# uC_pwr.net
KiCad netlist of a schematic drawn in Altium Designer
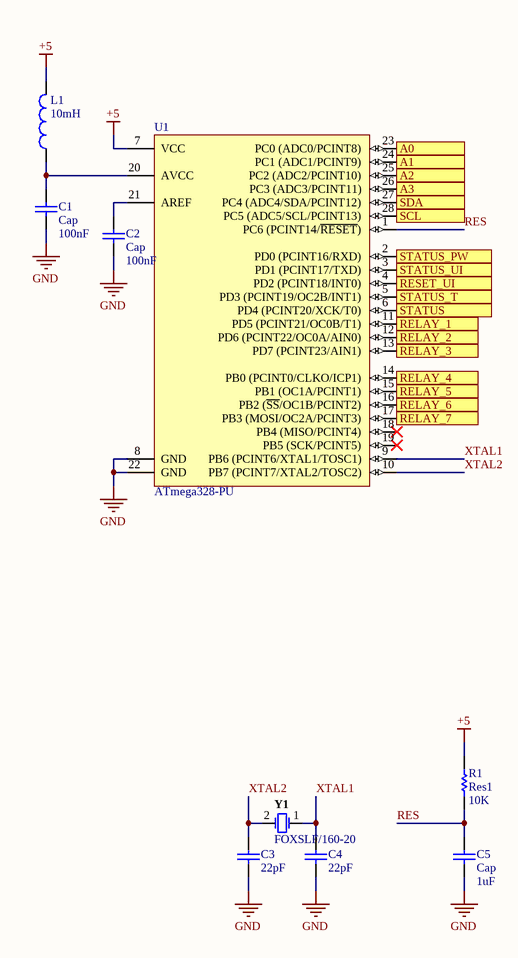
[diagram p0: uC_pwr.SchDoc]

(export (version "E")
  (design (tool "Eeschema 10.0.6"))
  (components
    (comp (ref "C1")
      (value "Cap")
      (footprint "RAD-0.3")
      (description "Capacitor")
      (fields (field (name "ALTIUM_VALUE") "100nF") (field (name "PUBLISHER") "Altium Limited"))
      (libsource (lib "Miscellaneous Devices") (part "Cap"))
    )
    (comp (ref "C2")
      (value "Cap")
      (footprint "RAD-0.3")
      (description "Capacitor")
      (fields (field (name "ALTIUM_VALUE") "100nF") (field (name "PUBLISHER") "Altium Limited"))
      (libsource (lib "Miscellaneous Devices") (part "Cap"))
    )
    (comp (ref "C3")
      (value "22pF")
      (footprint "RAD-0.3")
      (description "Capacitor")
      (fields (field (name "Comment") "Cap") (field (name "PUBLISHER") "Altium Limited"))
      (libsource (lib "Miscellaneous Devices") (part "Cap"))
    )
    (comp (ref "C4")
      (value "22pF")
      (footprint "RAD-0.3")
      (description "Capacitor")
      (fields (field (name "Comment") "Cap") (field (name "PUBLISHER") "Altium Limited"))
      (libsource (lib "Miscellaneous Devices") (part "Cap"))
    )
    (comp (ref "C5")
      (value "Cap")
      (footprint "RAD-0.3")
      (description "Capacitor")
      (fields (field (name "ALTIUM_VALUE") "1uF") (field (name "PUBLISHER") "Altium Limited"))
      (libsource (lib "Miscellaneous Devices") (part "Cap"))
    )
    (comp (ref "L1")
      (value "10mH")
      (footprint "INDR62-500-1100X850X1100")
      (description "Radial Inductor, 10 uH, +/- 10%, 3 A, -55 to 105 degC, 2-Pin THD, RoHS, Bulk")
      (libsource (lib "Altium Content Vault") (part "IND-2"))
    )
    (comp (ref "R1")
      (value "Res1")
      (footprint "AXIAL-0.3")
      (description "Resistor")
      (fields (field (name "ALTIUM_VALUE") "10K") (field (name "PUBLISHER") "Altium Limited"))
      (libsource (lib "Miscellaneous Devices") (part "Res1"))
    )
    (comp (ref "U1")
      (value "ATmega328-PU")
      (footprint "28P3")
      (libsource (lib "Altium Content Vault") (part "MC-8B-ATM48-IL28"))
    )
    (comp (ref "Y1")
      (value "FOXSLF/160-20")
      (footprint "FOX-FOXSLF160-20")
      (description "Resistance Weld Thru-Hole Crystal, 16 MHz, -20 to 70 degC, 2-Pin THD, RoHS, Bulk")
      (fields (field (name "TOLERANCE") "1%"))
      (libsource (lib "Altium Content Vault") (part "XTAL-1-2-2"))
    )
  )
  (nets
    (net (code "1") (name "+5") (class "Default")
      (node (ref "L1") (pin "2") (pinfunction "2_2") (pintype "passive"))
      (node (ref "R1") (pin "2") (pinfunction "2_2") (pintype "passive"))
      (node (ref "U1") (pin "7") (pinfunction "VCC_7") (pintype "power_in"))
    )
    (net (code "2") (name "/A0") (class "Default")
      (node (ref "U1") (pin "23") (pinfunction "PC0_(ADC0/PCINT8)_23") (pintype "bidirectional"))
    )
    (net (code "3") (name "/A1") (class "Default")
      (node (ref "U1") (pin "24") (pinfunction "PC1_(ADC1/PCINT9)_24") (pintype "bidirectional"))
    )
    (net (code "4") (name "/A2") (class "Default")
      (node (ref "U1") (pin "25") (pinfunction "PC2_(ADC2/PCINT10)_25") (pintype "bidirectional"))
    )
    (net (code "5") (name "/A3") (class "Default")
      (node (ref "U1") (pin "26") (pinfunction "PC3_(ADC3/PCINT11)_26") (pintype "bidirectional"))
    )
    (net (code "6") (name "/RELAY_1") (class "Default")
      (node (ref "U1") (pin "11") (pinfunction "PD5_(PCINT21/OC0B/T1)_11") (pintype "bidirectional"))
    )
    (net (code "7") (name "/RELAY_2") (class "Default")
      (node (ref "U1") (pin "12") (pinfunction "PD6_(PCINT22/OC0A/AIN0)_12") (pintype "bidirectional"))
    )
    (net (code "8") (name "/RELAY_3") (class "Default")
      (node (ref "U1") (pin "13") (pinfunction "PD7_(PCINT23/AIN1)_13") (pintype "bidirectional"))
    )
    (net (code "9") (name "/RELAY_4") (class "Default")
      (node (ref "U1") (pin "14") (pinfunction "PB0_(PCINT0/CLKO/ICP1)_14") (pintype "bidirectional"))
    )
    (net (code "10") (name "/RELAY_5") (class "Default")
      (node (ref "U1") (pin "15") (pinfunction "PB1_(OC1A/PCINT1)_15") (pintype "bidirectional"))
    )
    (net (code "11") (name "/RELAY_6") (class "Default")
      (node (ref "U1") (pin "16") (pinfunction "PB2_(~{SS}/OC1B/PCINT2)_16") (pintype "bidirectional"))
    )
    (net (code "12") (name "/RELAY_7") (class "Default")
      (node (ref "U1") (pin "17") (pinfunction "PB3_(MOSI/OC2A/PCINT3)_17") (pintype "bidirectional"))
    )
    (net (code "13") (name "/RES") (class "Default")
      (node (ref "C5") (pin "2") (pinfunction "2_2") (pintype "passive"))
      (node (ref "R1") (pin "1") (pinfunction "1_1") (pintype "passive"))
      (node (ref "U1") (pin "1") (pinfunction "PC6_(PCINT14/~{RESET})_1") (pintype "bidirectional"))
    )
    (net (code "14") (name "/RESET_UI") (class "Default")
      (node (ref "U1") (pin "4") (pinfunction "PD2_(PCINT18/INT0)_4") (pintype "bidirectional"))
    )
    (net (code "15") (name "/SCL") (class "Default")
      (node (ref "U1") (pin "28") (pinfunction "PC5_(ADC5/SCL/PCINT13)_28") (pintype "bidirectional"))
    )
    (net (code "16") (name "/SDA") (class "Default")
      (node (ref "U1") (pin "27") (pinfunction "PC4_(ADC4/SDA/PCINT12)_27") (pintype "bidirectional"))
    )
    (net (code "17") (name "/STATUS") (class "Default")
      (node (ref "U1") (pin "6") (pinfunction "PD4_(PCINT20/XCK/T0)_6") (pintype "bidirectional"))
    )
    (net (code "18") (name "/STATUS_PW") (class "Default")
      (node (ref "U1") (pin "2") (pinfunction "PD0_(PCINT16/RXD)_2") (pintype "bidirectional"))
    )
    (net (code "19") (name "/STATUS_T") (class "Default")
      (node (ref "U1") (pin "5") (pinfunction "PD3_(PCINT19/OC2B/INT1)_5") (pintype "bidirectional"))
    )
    (net (code "20") (name "/STATUS_UI") (class "Default")
      (node (ref "U1") (pin "3") (pinfunction "PD1_(PCINT17/TXD)_3") (pintype "bidirectional"))
    )
    (net (code "21") (name "/XTAL1") (class "Default")
      (node (ref "C4") (pin "2") (pinfunction "2_2") (pintype "passive"))
      (node (ref "U1") (pin "9") (pinfunction "PB6_(PCINT6/XTAL1/TOSC1)_9") (pintype "bidirectional"))
      (node (ref "Y1") (pin "1") (pinfunction "1_1") (pintype "passive"))
    )
    (net (code "22") (name "/XTAL2") (class "Default")
      (node (ref "C3") (pin "2") (pinfunction "2_2") (pintype "passive"))
      (node (ref "U1") (pin "10") (pinfunction "PB7_(PCINT7/XTAL2/TOSC2)_10") (pintype "bidirectional"))
      (node (ref "Y1") (pin "2") (pinfunction "2_2") (pintype "passive"))
    )
    (net (code "23") (name "GND") (class "Default")
      (node (ref "C1") (pin "1") (pinfunction "1_1") (pintype "passive"))
      (node (ref "C2") (pin "1") (pinfunction "1_1") (pintype "passive"))
      (node (ref "C3") (pin "1") (pinfunction "1_1") (pintype "passive"))
      (node (ref "C4") (pin "1") (pinfunction "1_1") (pintype "passive"))
      (node (ref "C5") (pin "1") (pinfunction "1_1") (pintype "passive"))
      (node (ref "U1") (pin "22") (pinfunction "GND_22") (pintype "power_in"))
      (node (ref "U1") (pin "8") (pinfunction "GND_8") (pintype "power_in"))
    )
    (net (code "24") (name "Net-(U1-AREF)") (class "Default")
      (node (ref "C2") (pin "2") (pinfunction "2_2") (pintype "passive"))
      (node (ref "U1") (pin "21") (pinfunction "AREF_21") (pintype "power_in"))
    )
    (net (code "25") (name "Net-(U1-AVCC)") (class "Default")
      (node (ref "C1") (pin "2") (pinfunction "2_2") (pintype "passive"))
      (node (ref "L1") (pin "1") (pinfunction "1_1") (pintype "passive"))
      (node (ref "U1") (pin "20") (pinfunction "AVCC_20") (pintype "power_in"))
    )
    (net (code "26") (name "unconnected-(U1-PB4_(MISO{slash}PCINT4)-Pad18)") (class "Default")
      (node (ref "U1") (pin "18") (pinfunction "PB4_(MISO/PCINT4)_18") (pintype "bidirectional+no_connect"))
    )
    (net (code "27") (name "unconnected-(U1-PB5_(SCK{slash}PCINT5)-Pad19)") (class "Default")
      (node (ref "U1") (pin "19") (pinfunction "PB5_(SCK/PCINT5)_19") (pintype "bidirectional+no_connect"))
    )
  )
)
